# Morpheus_LED2.net
KiCad netlist of a schematic drawn in Altium Designer
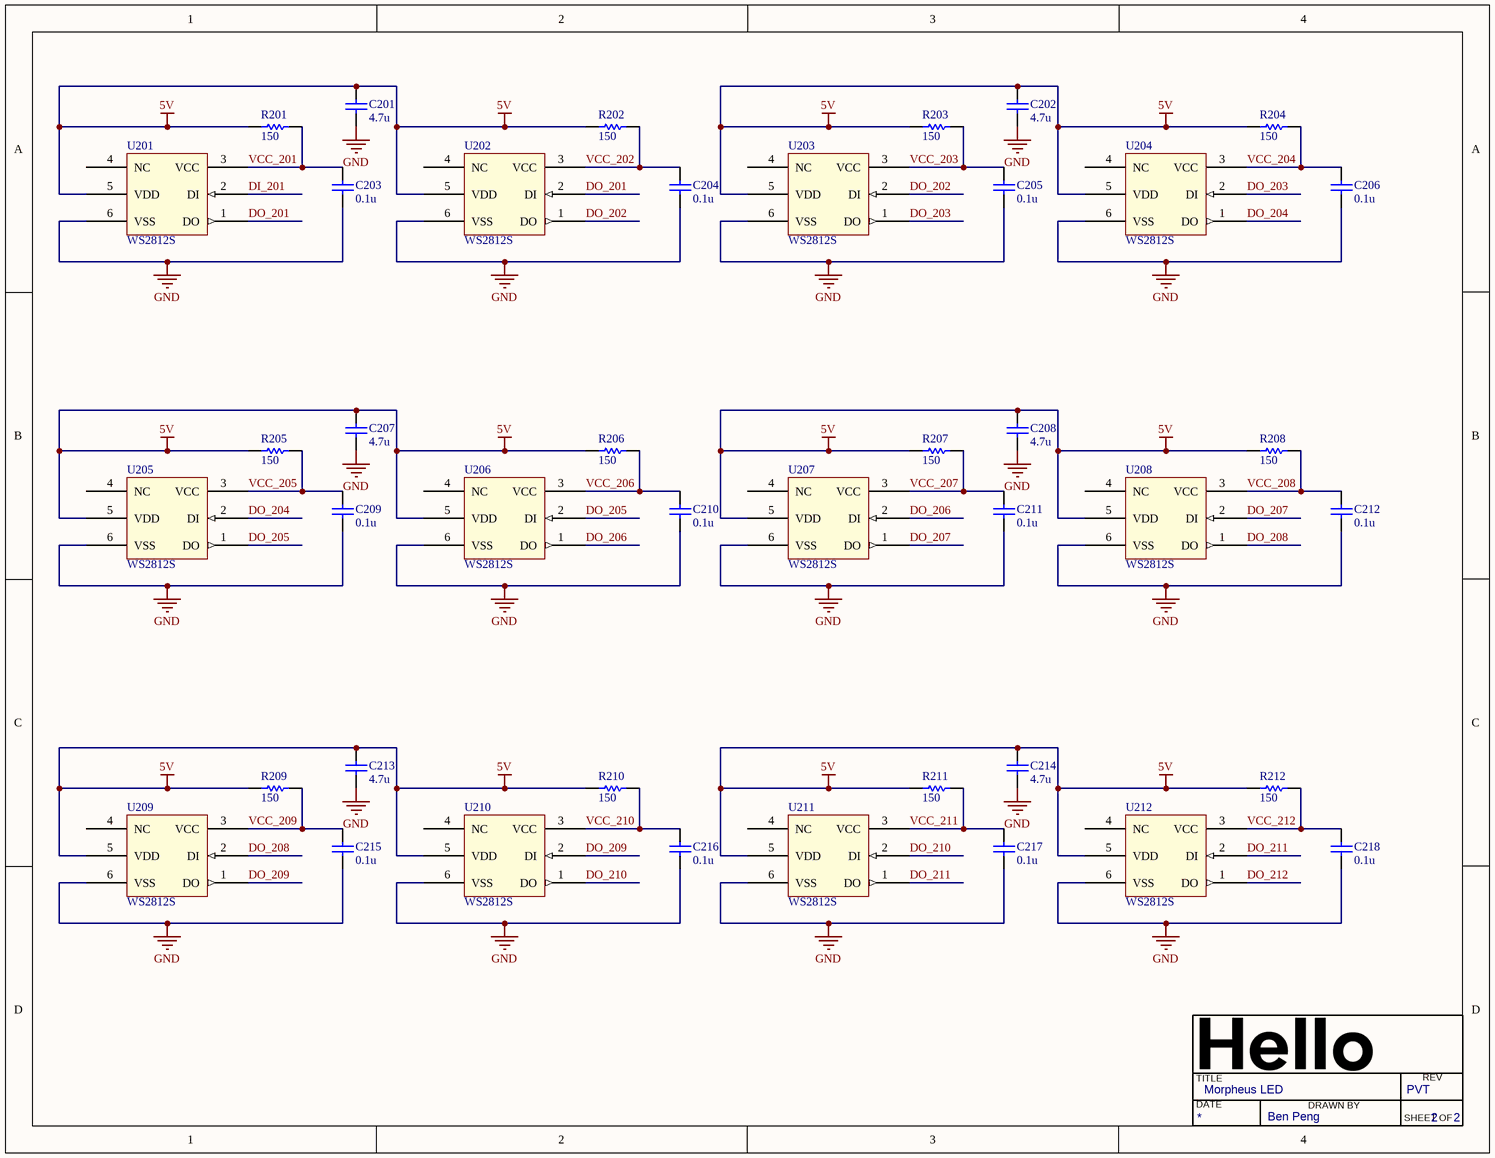
[diagram p0: Morpheus_LED2.SchDoc]

(export (version "E")
  (design (tool "Eeschema 10.0.6"))
  (components
    (comp (ref "C201")
      (value "4.7u")
      (footprint "CAP0402_SENSE_DVT")
      (description "Chip capacitor")
      (fields (field (name "TOLERANCE") "10%") (field (name "VOLTAGE") "10V"))
      (libsource (lib "Hello") (part "C_4.7u_10_10_JB_0402"))
    )
    (comp (ref "C202")
      (value "4.7u")
      (footprint "CAP0402_SENSE_DVT")
      (description "Chip capacitor")
      (fields (field (name "TOLERANCE") "10%") (field (name "VOLTAGE") "10V"))
      (libsource (lib "Hello") (part "C_4.7u_10_10_JB_0402"))
    )
    (comp (ref "C203")
      (value "0.1u")
      (footprint "CAP0402_SENSE_DVT")
      (description "Chip capacitor")
      (fields (field (name "TOLERANCE") "10%") (field (name "VOLTAGE") "50V"))
      (libsource (lib "Hello") (part "C_0.1u_10_50_X7R_0402"))
    )
    (comp (ref "C204")
      (value "0.1u")
      (footprint "CAP0402_SENSE_DVT")
      (description "Chip capacitor")
      (fields (field (name "TOLERANCE") "10%") (field (name "VOLTAGE") "50V"))
      (libsource (lib "Hello") (part "C_0.1u_10_50_X7R_0402"))
    )
    (comp (ref "C205")
      (value "0.1u")
      (footprint "CAP0402_SENSE_DVT")
      (description "Chip capacitor")
      (fields (field (name "TOLERANCE") "10%") (field (name "VOLTAGE") "50V"))
      (libsource (lib "Hello") (part "C_0.1u_10_50_X7R_0402"))
    )
    (comp (ref "C206")
      (value "0.1u")
      (footprint "CAP0402_SENSE_DVT")
      (description "Chip capacitor")
      (fields (field (name "TOLERANCE") "10%") (field (name "VOLTAGE") "50V"))
      (libsource (lib "Hello") (part "C_0.1u_10_50_X7R_0402"))
    )
    (comp (ref "C207")
      (value "4.7u")
      (footprint "CAP0402_SENSE_DVT")
      (description "Chip capacitor")
      (fields (field (name "TOLERANCE") "10%") (field (name "VOLTAGE") "10V"))
      (libsource (lib "Hello") (part "C_4.7u_10_10_JB_0402"))
    )
    (comp (ref "C208")
      (value "4.7u")
      (footprint "CAP0402_SENSE_DVT")
      (description "Chip capacitor")
      (fields (field (name "TOLERANCE") "10%") (field (name "VOLTAGE") "10V"))
      (libsource (lib "Hello") (part "C_4.7u_10_10_JB_0402"))
    )
    (comp (ref "C209")
      (value "0.1u")
      (footprint "CAP0402_SENSE_DVT")
      (description "Chip capacitor")
      (fields (field (name "TOLERANCE") "10%") (field (name "VOLTAGE") "50V"))
      (libsource (lib "Hello") (part "C_0.1u_10_50_X7R_0402"))
    )
    (comp (ref "C210")
      (value "0.1u")
      (footprint "CAP0402_SENSE_DVT")
      (description "Chip capacitor")
      (fields (field (name "TOLERANCE") "10%") (field (name "VOLTAGE") "50V"))
      (libsource (lib "Hello") (part "C_0.1u_10_50_X7R_0402"))
    )
    (comp (ref "C211")
      (value "0.1u")
      (footprint "CAP0402_SENSE_DVT")
      (description "Chip capacitor")
      (fields (field (name "TOLERANCE") "10%") (field (name "VOLTAGE") "50V"))
      (libsource (lib "Hello") (part "C_0.1u_10_50_X7R_0402"))
    )
    (comp (ref "C212")
      (value "0.1u")
      (footprint "CAP0402_SENSE_DVT")
      (description "Chip capacitor")
      (fields (field (name "TOLERANCE") "10%") (field (name "VOLTAGE") "50V"))
      (libsource (lib "Hello") (part "C_0.1u_10_50_X7R_0402"))
    )
    (comp (ref "C213")
      (value "4.7u")
      (footprint "CAP0402_SENSE_DVT")
      (description "Chip capacitor")
      (fields (field (name "TOLERANCE") "10%") (field (name "VOLTAGE") "10V"))
      (libsource (lib "Hello") (part "C_4.7u_10_10_JB_0402"))
    )
    (comp (ref "C214")
      (value "4.7u")
      (footprint "CAP0402_SENSE_DVT")
      (description "Chip capacitor")
      (fields (field (name "TOLERANCE") "10%") (field (name "VOLTAGE") "10V"))
      (libsource (lib "Hello") (part "C_4.7u_10_10_JB_0402"))
    )
    (comp (ref "C215")
      (value "0.1u")
      (footprint "CAP0402_SENSE_DVT")
      (description "Chip capacitor")
      (fields (field (name "TOLERANCE") "10%") (field (name "VOLTAGE") "50V"))
      (libsource (lib "Hello") (part "C_0.1u_10_50_X7R_0402"))
    )
    (comp (ref "C216")
      (value "0.1u")
      (footprint "CAP0402_SENSE_DVT")
      (description "Chip capacitor")
      (fields (field (name "TOLERANCE") "10%") (field (name "VOLTAGE") "50V"))
      (libsource (lib "Hello") (part "C_0.1u_10_50_X7R_0402"))
    )
    (comp (ref "C217")
      (value "0.1u")
      (footprint "CAP0402_SENSE_DVT")
      (description "Chip capacitor")
      (fields (field (name "TOLERANCE") "10%") (field (name "VOLTAGE") "50V"))
      (libsource (lib "Hello") (part "C_0.1u_10_50_X7R_0402"))
    )
    (comp (ref "C218")
      (value "0.1u")
      (footprint "CAP0402_SENSE_DVT")
      (description "Chip capacitor")
      (fields (field (name "TOLERANCE") "10%") (field (name "VOLTAGE") "50V"))
      (libsource (lib "Hello") (part "C_0.1u_10_50_X7R_0402"))
    )
    (comp (ref "R201")
      (value "150")
      (footprint "RES0402_SENSE_DVT")
      (description "Chip Resistor")
      (fields (field (name "TOLERANCE") "1 %") (field (name "POWER") "0.1 W"))
      (libsource (lib "Hello") (part "R_150_1_0.1_0402"))
    )
    (comp (ref "R202")
      (value "150")
      (footprint "RES0402_SENSE_DVT")
      (description "Chip Resistor")
      (fields (field (name "TOLERANCE") "1 %") (field (name "POWER") "0.1 W"))
      (libsource (lib "Hello") (part "R_150_1_0.1_0402"))
    )
    (comp (ref "R203")
      (value "150")
      (footprint "RES0402_SENSE_DVT")
      (description "Chip Resistor")
      (fields (field (name "TOLERANCE") "1 %") (field (name "POWER") "0.1 W"))
      (libsource (lib "Hello") (part "R_150_1_0.1_0402"))
    )
    (comp (ref "R204")
      (value "150")
      (footprint "RES0402_SENSE_DVT")
      (description "Chip Resistor")
      (fields (field (name "TOLERANCE") "1 %") (field (name "POWER") "0.1 W"))
      (libsource (lib "Hello") (part "R_150_1_0.1_0402"))
    )
    (comp (ref "R205")
      (value "150")
      (footprint "RES0402_SENSE_DVT")
      (description "Chip Resistor")
      (fields (field (name "TOLERANCE") "1 %") (field (name "POWER") "0.1 W"))
      (libsource (lib "Hello") (part "R_150_1_0.1_0402"))
    )
    (comp (ref "R206")
      (value "150")
      (footprint "RES0402_SENSE_DVT")
      (description "Chip Resistor")
      (fields (field (name "TOLERANCE") "1 %") (field (name "POWER") "0.1 W"))
      (libsource (lib "Hello") (part "R_150_1_0.1_0402"))
    )
    (comp (ref "R207")
      (value "150")
      (footprint "RES0402_SENSE_DVT")
      (description "Chip Resistor")
      (fields (field (name "TOLERANCE") "1 %") (field (name "POWER") "0.1 W"))
      (libsource (lib "Hello") (part "R_150_1_0.1_0402"))
    )
    (comp (ref "R208")
      (value "150")
      (footprint "RES0402_SENSE_DVT")
      (description "Chip Resistor")
      (fields (field (name "TOLERANCE") "1 %") (field (name "POWER") "0.1 W"))
      (libsource (lib "Hello") (part "R_150_1_0.1_0402"))
    )
    (comp (ref "R209")
      (value "150")
      (footprint "RES0402_SENSE_DVT")
      (description "Chip Resistor")
      (fields (field (name "TOLERANCE") "1 %") (field (name "POWER") "0.1 W"))
      (libsource (lib "Hello") (part "R_150_1_0.1_0402"))
    )
    (comp (ref "R210")
      (value "150")
      (footprint "RES0402_SENSE_DVT")
      (description "Chip Resistor")
      (fields (field (name "TOLERANCE") "1 %") (field (name "POWER") "0.1 W"))
      (libsource (lib "Hello") (part "R_150_1_0.1_0402"))
    )
    (comp (ref "R211")
      (value "150")
      (footprint "RES0402_SENSE_DVT")
      (description "Chip Resistor")
      (fields (field (name "TOLERANCE") "1 %") (field (name "POWER") "0.1 W"))
      (libsource (lib "Hello") (part "R_150_1_0.1_0402"))
    )
    (comp (ref "R212")
      (value "150")
      (footprint "RES0402_SENSE_DVT")
      (description "Chip Resistor")
      (fields (field (name "TOLERANCE") "1 %") (field (name "POWER") "0.1 W"))
      (libsource (lib "Hello") (part "R_150_1_0.1_0402"))
    )
    (comp (ref "U201")
      (value "WS2812S")
      (footprint "6PIN_WS2812")
      (description "WS2812S Intelligent control LED integrated light source")
      (libsource (lib "Hello") (part "WS2812S"))
    )
    (comp (ref "U202")
      (value "WS2812S")
      (footprint "6PIN_WS2812")
      (description "WS2812S Intelligent control LED integrated light source")
      (libsource (lib "Hello") (part "WS2812S"))
    )
    (comp (ref "U203")
      (value "WS2812S")
      (footprint "6PIN_WS2812")
      (description "WS2812S Intelligent control LED integrated light source")
      (libsource (lib "Hello") (part "WS2812S"))
    )
    (comp (ref "U204")
      (value "WS2812S")
      (footprint "6PIN_WS2812")
      (description "WS2812S Intelligent control LED integrated light source")
      (libsource (lib "Hello") (part "WS2812S"))
    )
    (comp (ref "U205")
      (value "WS2812S")
      (footprint "6PIN_WS2812")
      (description "WS2812S Intelligent control LED integrated light source")
      (libsource (lib "Hello") (part "WS2812S"))
    )
    (comp (ref "U206")
      (value "WS2812S")
      (footprint "6PIN_WS2812")
      (description "WS2812S Intelligent control LED integrated light source")
      (libsource (lib "Hello") (part "WS2812S"))
    )
    (comp (ref "U207")
      (value "WS2812S")
      (footprint "6PIN_WS2812")
      (description "WS2812S Intelligent control LED integrated light source")
      (libsource (lib "Hello") (part "WS2812S"))
    )
    (comp (ref "U208")
      (value "WS2812S")
      (footprint "6PIN_WS2812")
      (description "WS2812S Intelligent control LED integrated light source")
      (libsource (lib "Hello") (part "WS2812S"))
    )
    (comp (ref "U209")
      (value "WS2812S")
      (footprint "6PIN_WS2812")
      (description "WS2812S Intelligent control LED integrated light source")
      (libsource (lib "Hello") (part "WS2812S"))
    )
    (comp (ref "U210")
      (value "WS2812S")
      (footprint "6PIN_WS2812")
      (description "WS2812S Intelligent control LED integrated light source")
      (libsource (lib "Hello") (part "WS2812S"))
    )
    (comp (ref "U211")
      (value "WS2812S")
      (footprint "6PIN_WS2812")
      (description "WS2812S Intelligent control LED integrated light source")
      (libsource (lib "Hello") (part "WS2812S"))
    )
    (comp (ref "U212")
      (value "WS2812S")
      (footprint "6PIN_WS2812")
      (description "WS2812S Intelligent control LED integrated light source")
      (libsource (lib "Hello") (part "WS2812S"))
    )
  )
  (nets
    (net (code "1") (name "/DI_201") (class "Default")
      (node (ref "U201") (pin "2") (pinfunction "DI_2") (pintype "input"))
    )
    (net (code "2") (name "/DO_201") (class "Default")
      (node (ref "U201") (pin "1") (pinfunction "DO_1") (pintype "output"))
      (node (ref "U202") (pin "2") (pinfunction "DI_2") (pintype "input"))
    )
    (net (code "3") (name "/DO_202") (class "Default")
      (node (ref "U202") (pin "1") (pinfunction "DO_1") (pintype "output"))
      (node (ref "U203") (pin "2") (pinfunction "DI_2") (pintype "input"))
    )
    (net (code "4") (name "/DO_203") (class "Default")
      (node (ref "U203") (pin "1") (pinfunction "DO_1") (pintype "output"))
      (node (ref "U204") (pin "2") (pinfunction "DI_2") (pintype "input"))
    )
    (net (code "5") (name "/DO_204") (class "Default")
      (node (ref "U204") (pin "1") (pinfunction "DO_1") (pintype "output"))
      (node (ref "U205") (pin "2") (pinfunction "DI_2") (pintype "input"))
    )
    (net (code "6") (name "/DO_205") (class "Default")
      (node (ref "U205") (pin "1") (pinfunction "DO_1") (pintype "output"))
      (node (ref "U206") (pin "2") (pinfunction "DI_2") (pintype "input"))
    )
    (net (code "7") (name "/DO_206") (class "Default")
      (node (ref "U206") (pin "1") (pinfunction "DO_1") (pintype "output"))
      (node (ref "U207") (pin "2") (pinfunction "DI_2") (pintype "input"))
    )
    (net (code "8") (name "/DO_207") (class "Default")
      (node (ref "U207") (pin "1") (pinfunction "DO_1") (pintype "output"))
      (node (ref "U208") (pin "2") (pinfunction "DI_2") (pintype "input"))
    )
    (net (code "9") (name "/DO_208") (class "Default")
      (node (ref "U208") (pin "1") (pinfunction "DO_1") (pintype "output"))
      (node (ref "U209") (pin "2") (pinfunction "DI_2") (pintype "input"))
    )
    (net (code "10") (name "/DO_209") (class "Default")
      (node (ref "U209") (pin "1") (pinfunction "DO_1") (pintype "output"))
      (node (ref "U210") (pin "2") (pinfunction "DI_2") (pintype "input"))
    )
    (net (code "11") (name "/DO_210") (class "Default")
      (node (ref "U210") (pin "1") (pinfunction "DO_1") (pintype "output"))
      (node (ref "U211") (pin "2") (pinfunction "DI_2") (pintype "input"))
    )
    (net (code "12") (name "/DO_211") (class "Default")
      (node (ref "U211") (pin "1") (pinfunction "DO_1") (pintype "output"))
      (node (ref "U212") (pin "2") (pinfunction "DI_2") (pintype "input"))
    )
    (net (code "13") (name "/DO_212") (class "Default")
      (node (ref "U212") (pin "1") (pinfunction "DO_1") (pintype "output"))
    )
    (net (code "14") (name "/VCC_201") (class "Default")
      (node (ref "C203") (pin "2") (pinfunction "2_2") (pintype "passive"))
      (node (ref "R201") (pin "1") (pinfunction "1_1") (pintype "passive"))
      (node (ref "U201") (pin "3") (pinfunction "VCC_3") (pintype "power_in"))
    )
    (net (code "15") (name "/VCC_202") (class "Default")
      (node (ref "C204") (pin "2") (pinfunction "2_2") (pintype "passive"))
      (node (ref "R202") (pin "1") (pinfunction "1_1") (pintype "passive"))
      (node (ref "U202") (pin "3") (pinfunction "VCC_3") (pintype "power_in"))
    )
    (net (code "16") (name "/VCC_203") (class "Default")
      (node (ref "C205") (pin "2") (pinfunction "2_2") (pintype "passive"))
      (node (ref "R203") (pin "1") (pinfunction "1_1") (pintype "passive"))
      (node (ref "U203") (pin "3") (pinfunction "VCC_3") (pintype "power_in"))
    )
    (net (code "17") (name "/VCC_204") (class "Default")
      (node (ref "C206") (pin "2") (pinfunction "2_2") (pintype "passive"))
      (node (ref "R204") (pin "1") (pinfunction "1_1") (pintype "passive"))
      (node (ref "U204") (pin "3") (pinfunction "VCC_3") (pintype "power_in"))
    )
    (net (code "18") (name "/VCC_205") (class "Default")
      (node (ref "C209") (pin "2") (pinfunction "2_2") (pintype "passive"))
      (node (ref "R205") (pin "1") (pinfunction "1_1") (pintype "passive"))
      (node (ref "U205") (pin "3") (pinfunction "VCC_3") (pintype "power_in"))
    )
    (net (code "19") (name "/VCC_206") (class "Default")
      (node (ref "C210") (pin "2") (pinfunction "2_2") (pintype "passive"))
      (node (ref "R206") (pin "1") (pinfunction "1_1") (pintype "passive"))
      (node (ref "U206") (pin "3") (pinfunction "VCC_3") (pintype "power_in"))
    )
    (net (code "20") (name "/VCC_207") (class "Default")
      (node (ref "C211") (pin "2") (pinfunction "2_2") (pintype "passive"))
      (node (ref "R207") (pin "1") (pinfunction "1_1") (pintype "passive"))
      (node (ref "U207") (pin "3") (pinfunction "VCC_3") (pintype "power_in"))
    )
    (net (code "21") (name "/VCC_208") (class "Default")
      (node (ref "C212") (pin "2") (pinfunction "2_2") (pintype "passive"))
      (node (ref "R208") (pin "1") (pinfunction "1_1") (pintype "passive"))
      (node (ref "U208") (pin "3") (pinfunction "VCC_3") (pintype "power_in"))
    )
    (net (code "22") (name "/VCC_209") (class "Default")
      (node (ref "C215") (pin "2") (pinfunction "2_2") (pintype "passive"))
      (node (ref "R209") (pin "1") (pinfunction "1_1") (pintype "passive"))
      (node (ref "U209") (pin "3") (pinfunction "VCC_3") (pintype "power_in"))
    )
    (net (code "23") (name "/VCC_210") (class "Default")
      (node (ref "C216") (pin "2") (pinfunction "2_2") (pintype "passive"))
      (node (ref "R210") (pin "1") (pinfunction "1_1") (pintype "passive"))
      (node (ref "U210") (pin "3") (pinfunction "VCC_3") (pintype "power_in"))
    )
    (net (code "24") (name "/VCC_211") (class "Default")
      (node (ref "C217") (pin "2") (pinfunction "2_2") (pintype "passive"))
      (node (ref "R211") (pin "1") (pinfunction "1_1") (pintype "passive"))
      (node (ref "U211") (pin "3") (pinfunction "VCC_3") (pintype "power_in"))
    )
    (net (code "25") (name "/VCC_212") (class "Default")
      (node (ref "C218") (pin "2") (pinfunction "2_2") (pintype "passive"))
      (node (ref "R212") (pin "1") (pinfunction "1_1") (pintype "passive"))
      (node (ref "U212") (pin "3") (pinfunction "VCC_3") (pintype "power_in"))
    )
    (net (code "26") (name "5V") (class "Default")
      (node (ref "C201") (pin "2") (pinfunction "2_2") (pintype "passive"))
      (node (ref "C202") (pin "2") (pinfunction "2_2") (pintype "passive"))
      (node (ref "C207") (pin "2") (pinfunction "2_2") (pintype "passive"))
      (node (ref "C208") (pin "2") (pinfunction "2_2") (pintype "passive"))
      (node (ref "C213") (pin "2") (pinfunction "2_2") (pintype "passive"))
      (node (ref "C214") (pin "2") (pinfunction "2_2") (pintype "passive"))
      (node (ref "R201") (pin "2") (pinfunction "2_2") (pintype "passive"))
      (node (ref "R202") (pin "2") (pinfunction "2_2") (pintype "passive"))
      (node (ref "R203") (pin "2") (pinfunction "2_2") (pintype "passive"))
      (node (ref "R204") (pin "2") (pinfunction "2_2") (pintype "passive"))
      (node (ref "R205") (pin "2") (pinfunction "2_2") (pintype "passive"))
      (node (ref "R206") (pin "2") (pinfunction "2_2") (pintype "passive"))
      (node (ref "R207") (pin "2") (pinfunction "2_2") (pintype "passive"))
      (node (ref "R208") (pin "2") (pinfunction "2_2") (pintype "passive"))
      (node (ref "R209") (pin "2") (pinfunction "2_2") (pintype "passive"))
      (node (ref "R210") (pin "2") (pinfunction "2_2") (pintype "passive"))
      (node (ref "R211") (pin "2") (pinfunction "2_2") (pintype "passive"))
      (node (ref "R212") (pin "2") (pinfunction "2_2") (pintype "passive"))
      (node (ref "U201") (pin "5") (pinfunction "VDD_5") (pintype "power_in"))
      (node (ref "U202") (pin "5") (pinfunction "VDD_5") (pintype "power_in"))
      (node (ref "U203") (pin "5") (pinfunction "VDD_5") (pintype "power_in"))
      (node (ref "U204") (pin "5") (pinfunction "VDD_5") (pintype "power_in"))
      (node (ref "U205") (pin "5") (pinfunction "VDD_5") (pintype "power_in"))
      (node (ref "U206") (pin "5") (pinfunction "VDD_5") (pintype "power_in"))
      (node (ref "U207") (pin "5") (pinfunction "VDD_5") (pintype "power_in"))
      (node (ref "U208") (pin "5") (pinfunction "VDD_5") (pintype "power_in"))
      (node (ref "U209") (pin "5") (pinfunction "VDD_5") (pintype "power_in"))
      (node (ref "U210") (pin "5") (pinfunction "VDD_5") (pintype "power_in"))
      (node (ref "U211") (pin "5") (pinfunction "VDD_5") (pintype "power_in"))
      (node (ref "U212") (pin "5") (pinfunction "VDD_5") (pintype "power_in"))
    )
    (net (code "27") (name "GND") (class "Default")
      (node (ref "C201") (pin "1") (pinfunction "1_1") (pintype "passive"))
      (node (ref "C202") (pin "1") (pinfunction "1_1") (pintype "passive"))
      (node (ref "C203") (pin "1") (pinfunction "1_1") (pintype "passive"))
      (node (ref "C204") (pin "1") (pinfunction "1_1") (pintype "passive"))
      (node (ref "C205") (pin "1") (pinfunction "1_1") (pintype "passive"))
      (node (ref "C206") (pin "1") (pinfunction "1_1") (pintype "passive"))
      (node (ref "C207") (pin "1") (pinfunction "1_1") (pintype "passive"))
      (node (ref "C208") (pin "1") (pinfunction "1_1") (pintype "passive"))
      (node (ref "C209") (pin "1") (pinfunction "1_1") (pintype "passive"))
      (node (ref "C210") (pin "1") (pinfunction "1_1") (pintype "passive"))
      (node (ref "C211") (pin "1") (pinfunction "1_1") (pintype "passive"))
      (node (ref "C212") (pin "1") (pinfunction "1_1") (pintype "passive"))
      (node (ref "C213") (pin "1") (pinfunction "1_1") (pintype "passive"))
      (node (ref "C214") (pin "1") (pinfunction "1_1") (pintype "passive"))
      (node (ref "C215") (pin "1") (pinfunction "1_1") (pintype "passive"))
      (node (ref "C216") (pin "1") (pinfunction "1_1") (pintype "passive"))
      (node (ref "C217") (pin "1") (pinfunction "1_1") (pintype "passive"))
      (node (ref "C218") (pin "1") (pinfunction "1_1") (pintype "passive"))
      (node (ref "U201") (pin "6") (pinfunction "VSS_6") (pintype "power_in"))
      (node (ref "U202") (pin "6") (pinfunction "VSS_6") (pintype "power_in"))
      (node (ref "U203") (pin "6") (pinfunction "VSS_6") (pintype "power_in"))
      (node (ref "U204") (pin "6") (pinfunction "VSS_6") (pintype "power_in"))
      (node (ref "U205") (pin "6") (pinfunction "VSS_6") (pintype "power_in"))
      (node (ref "U206") (pin "6") (pinfunction "VSS_6") (pintype "power_in"))
      (node (ref "U207") (pin "6") (pinfunction "VSS_6") (pintype "power_in"))
      (node (ref "U208") (pin "6") (pinfunction "VSS_6") (pintype "power_in"))
      (node (ref "U209") (pin "6") (pinfunction "VSS_6") (pintype "power_in"))
      (node (ref "U210") (pin "6") (pinfunction "VSS_6") (pintype "power_in"))
      (node (ref "U211") (pin "6") (pinfunction "VSS_6") (pintype "power_in"))
      (node (ref "U212") (pin "6") (pinfunction "VSS_6") (pintype "power_in"))
    )
    (net (code "28") (name "unconnected-(U201-NC-Pad4)") (class "Default")
      (node (ref "U201") (pin "4") (pinfunction "NC_4") (pintype "passive"))
    )
    (net (code "29") (name "unconnected-(U202-NC-Pad4)") (class "Default")
      (node (ref "U202") (pin "4") (pinfunction "NC_4") (pintype "passive"))
    )
    (net (code "30") (name "unconnected-(U203-NC-Pad4)") (class "Default")
      (node (ref "U203") (pin "4") (pinfunction "NC_4") (pintype "passive"))
    )
    (net (code "31") (name "unconnected-(U204-NC-Pad4)") (class "Default")
      (node (ref "U204") (pin "4") (pinfunction "NC_4") (pintype "passive"))
    )
    (net (code "32") (name "unconnected-(U205-NC-Pad4)") (class "Default")
      (node (ref "U205") (pin "4") (pinfunction "NC_4") (pintype "passive"))
    )
    (net (code "33") (name "unconnected-(U206-NC-Pad4)") (class "Default")
      (node (ref "U206") (pin "4") (pinfunction "NC_4") (pintype "passive"))
    )
    (net (code "34") (name "unconnected-(U207-NC-Pad4)") (class "Default")
      (node (ref "U207") (pin "4") (pinfunction "NC_4") (pintype "passive"))
    )
    (net (code "35") (name "unconnected-(U208-NC-Pad4)") (class "Default")
      (node (ref "U208") (pin "4") (pinfunction "NC_4") (pintype "passive"))
    )
    (net (code "36") (name "unconnected-(U209-NC-Pad4)") (class "Default")
      (node (ref "U209") (pin "4") (pinfunction "NC_4") (pintype "passive"))
    )
    (net (code "37") (name "unconnected-(U210-NC-Pad4)") (class "Default")
      (node (ref "U210") (pin "4") (pinfunction "NC_4") (pintype "passive"))
    )
    (net (code "38") (name "unconnected-(U211-NC-Pad4)") (class "Default")
      (node (ref "U211") (pin "4") (pinfunction "NC_4") (pintype "passive"))
    )
    (net (code "39") (name "unconnected-(U212-NC-Pad4)") (class "Default")
      (node (ref "U212") (pin "4") (pinfunction "NC_4") (pintype "passive"))
    )
  )
)
